# 16_ch_sample-and-hold_card_v4.net
KiCad netlist of a schematic drawn in EAGLE
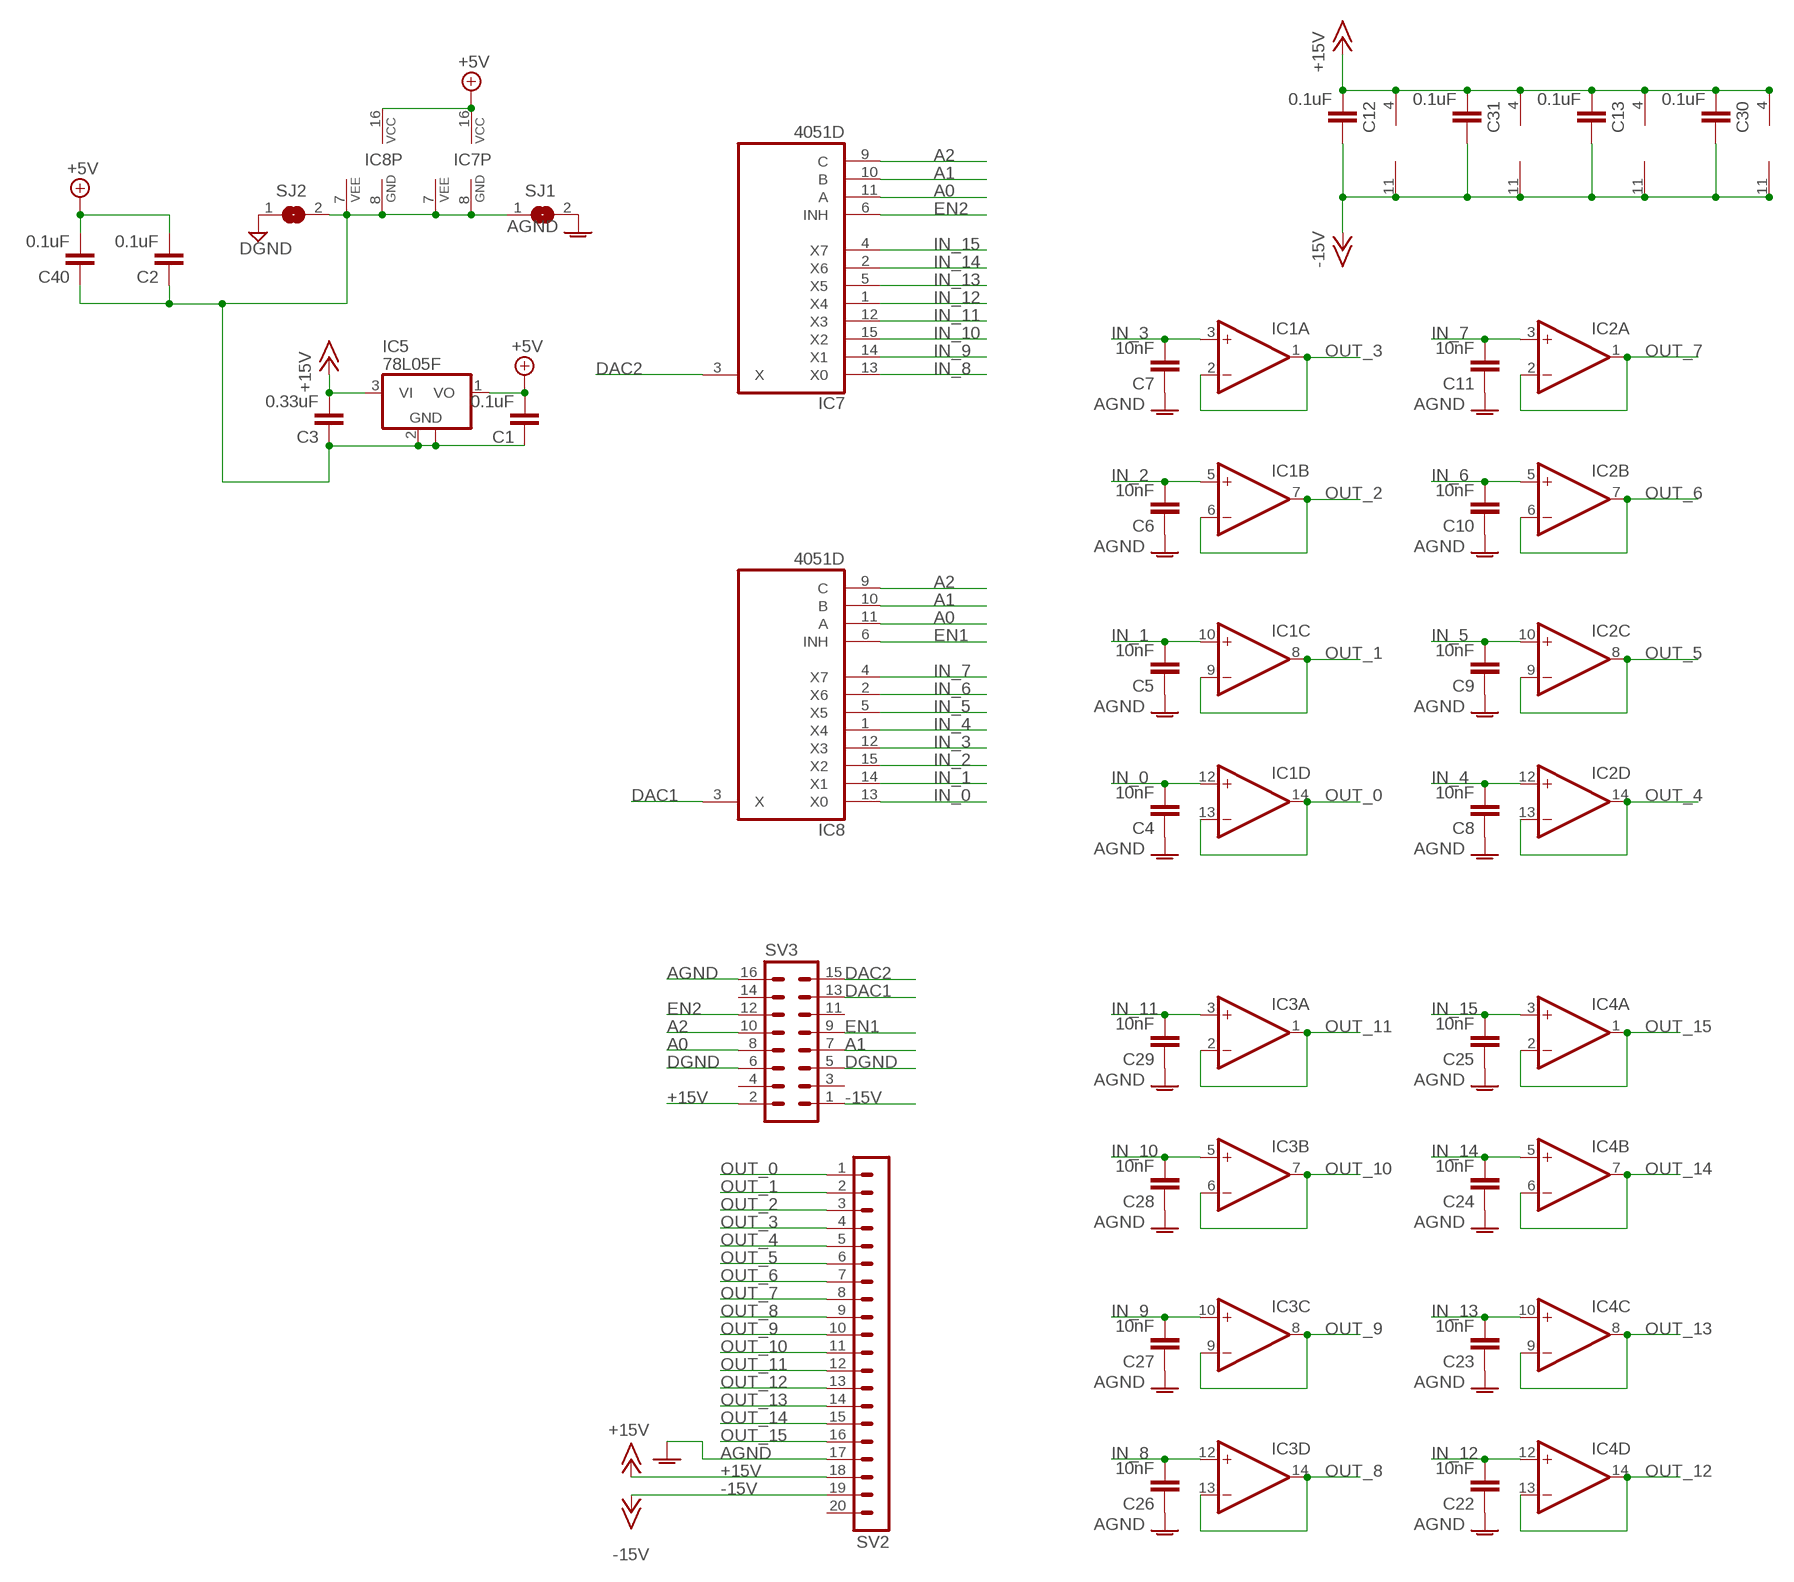
[diagram p0: schematic, sheet 1]

(export (version "E")
  (design (tool "Eeschema 10.0.6"))
  (components
    (comp (ref "C1")
      (value "0.1uF")
      (footprint "eagle-import:C0603")
      (libsource (lib "eagle-import") (part "C-EUC0603"))
    )
    (comp (ref "C2")
      (value "0.1uF")
      (footprint "eagle-import:C0603")
      (libsource (lib "eagle-import") (part "C-EUC0603"))
    )
    (comp (ref "C3")
      (value "0.33uF")
      (footprint "eagle-import:C0603")
      (libsource (lib "eagle-import") (part "C-EUC0603"))
    )
    (comp (ref "C4")
      (value "10nF")
      (footprint "eagle-import:C1206")
      (libsource (lib "eagle-import") (part "C-EUC1206"))
    )
    (comp (ref "C5")
      (value "10nF")
      (footprint "eagle-import:C1206")
      (libsource (lib "eagle-import") (part "C-EUC1206"))
    )
    (comp (ref "C6")
      (value "10nF")
      (footprint "eagle-import:C1206")
      (libsource (lib "eagle-import") (part "C-EUC1206"))
    )
    (comp (ref "C7")
      (value "10nF")
      (footprint "eagle-import:C1206")
      (libsource (lib "eagle-import") (part "C-EUC1206"))
    )
    (comp (ref "C8")
      (value "10nF")
      (footprint "eagle-import:C1206")
      (libsource (lib "eagle-import") (part "C-EUC1206"))
    )
    (comp (ref "C9")
      (value "10nF")
      (footprint "eagle-import:C1206")
      (libsource (lib "eagle-import") (part "C-EUC1206"))
    )
    (comp (ref "C10")
      (value "10nF")
      (footprint "eagle-import:C1206")
      (libsource (lib "eagle-import") (part "C-EUC1206"))
    )
    (comp (ref "C11")
      (value "10nF")
      (footprint "eagle-import:C1206")
      (libsource (lib "eagle-import") (part "C-EUC1206"))
    )
    (comp (ref "C12")
      (value "0.1uF")
      (footprint "eagle-import:C0603")
      (libsource (lib "eagle-import") (part "C-EUC0603"))
    )
    (comp (ref "C13")
      (value "0.1uF")
      (footprint "eagle-import:C0603")
      (libsource (lib "eagle-import") (part "C-EUC0603"))
    )
    (comp (ref "C22")
      (value "10nF")
      (footprint "eagle-import:C1206")
      (libsource (lib "eagle-import") (part "C-EUC1206"))
    )
    (comp (ref "C23")
      (value "10nF")
      (footprint "eagle-import:C1206")
      (libsource (lib "eagle-import") (part "C-EUC1206"))
    )
    (comp (ref "C24")
      (value "10nF")
      (footprint "eagle-import:C1206")
      (libsource (lib "eagle-import") (part "C-EUC1206"))
    )
    (comp (ref "C25")
      (value "10nF")
      (footprint "eagle-import:C1206")
      (libsource (lib "eagle-import") (part "C-EUC1206"))
    )
    (comp (ref "C26")
      (value "10nF")
      (footprint "eagle-import:C1206")
      (libsource (lib "eagle-import") (part "C-EUC1206"))
    )
    (comp (ref "C27")
      (value "10nF")
      (footprint "eagle-import:C1206")
      (libsource (lib "eagle-import") (part "C-EUC1206"))
    )
    (comp (ref "C28")
      (value "10nF")
      (footprint "eagle-import:C1206")
      (libsource (lib "eagle-import") (part "C-EUC1206"))
    )
    (comp (ref "C29")
      (value "10nF")
      (footprint "eagle-import:C1206")
      (libsource (lib "eagle-import") (part "C-EUC1206"))
    )
    (comp (ref "C30")
      (value "0.1uF")
      (footprint "eagle-import:C0603")
      (libsource (lib "eagle-import") (part "C-EUC0603"))
    )
    (comp (ref "C31")
      (value "0.1uF")
      (footprint "eagle-import:C0603")
      (libsource (lib "eagle-import") (part "C-EUC0603"))
    )
    (comp (ref "C40")
      (value "0.1uF")
      (footprint "eagle-import:C0603")
      (libsource (lib "eagle-import") (part "C-EUC0603"))
    )
    (comp (ref "IC1")
      (value "TL074D")
      (footprint "eagle-import:SO14")
      (libsource (lib "eagle-import") (part "TL074D"))
    )
    (comp (ref "IC2")
      (value "TL074D")
      (footprint "eagle-import:SO14")
      (libsource (lib "eagle-import") (part "TL074D"))
    )
    (comp (ref "IC3")
      (value "TL074D")
      (footprint "eagle-import:SO14")
      (libsource (lib "eagle-import") (part "TL074D"))
    )
    (comp (ref "IC4")
      (value "TL074D")
      (footprint "eagle-import:SO14")
      (libsource (lib "eagle-import") (part "TL074D"))
    )
    (comp (ref "IC5")
      (value "78L05F")
      (footprint "eagle-import:SOT89")
      (libsource (lib "eagle-import") (part "78LF05"))
    )
    (comp (ref "IC7")
      (value "4051D")
      (footprint "eagle-import:SO16")
      (libsource (lib "eagle-import") (part "4051D"))
    )
    (comp (ref "IC8")
      (value "4051D")
      (footprint "eagle-import:SO16")
      (libsource (lib "eagle-import") (part "4051D"))
    )
    (comp (ref "SJ1") (value "SJ") (footprint "eagle-import:SJ") (libsource (lib "eagle-import") (part "SJ")))
    (comp (ref "SJ2") (value "SJ") (footprint "eagle-import:SJ") (libsource (lib "eagle-import") (part "SJ")))
    (comp (ref "SV2")
      (value "MA20-1")
      (footprint "eagle-import:MA20-1")
      (libsource (lib "eagle-import") (part "MA20-1"))
    )
    (comp (ref "SV3")
      (value "MA08-2J")
      (footprint "eagle-import:MA08-2J")
      (libsource (lib "eagle-import") (part "MA08-2J"))
    )
  )
  (nets
    (net (code "1") (name "+5V") (class "Default")
      (node (ref "C1") (pin "2") (pinfunction "2_2") (pintype "passive"))
      (node (ref "C2") (pin "2") (pinfunction "2_2") (pintype "passive"))
      (node (ref "C40") (pin "2") (pinfunction "2_2") (pintype "passive"))
      (node (ref "IC5") (pin "1") (pinfunction "VO_1") (pintype "passive"))
      (node (ref "IC7") (pin "16") (pinfunction "VCC_16") (pintype "power_in"))
      (node (ref "IC8") (pin "16") (pinfunction "VCC_16") (pintype "power_in"))
    )
    (net (code "2") (name "+15V") (class "Default")
      (node (ref "C12") (pin "1") (pinfunction "1_1") (pintype "passive"))
      (node (ref "C13") (pin "1") (pinfunction "1_1") (pintype "passive"))
      (node (ref "C3") (pin "2") (pinfunction "2_2") (pintype "passive"))
      (node (ref "C30") (pin "1") (pinfunction "1_1") (pintype "passive"))
      (node (ref "C31") (pin "1") (pinfunction "1_1") (pintype "passive"))
      (node (ref "IC1") (pin "4") (pinfunction "V+_4") (pintype "power_in"))
      (node (ref "IC2") (pin "4") (pinfunction "V+_4") (pintype "power_in"))
      (node (ref "IC3") (pin "4") (pinfunction "V+_4") (pintype "power_in"))
      (node (ref "IC4") (pin "4") (pinfunction "V+_4") (pintype "power_in"))
      (node (ref "IC5") (pin "3") (pinfunction "VI_3") (pintype "input"))
      (node (ref "SV2") (pin "18") (pinfunction "18_18") (pintype "passive"))
      (node (ref "SV3") (pin "2") (pinfunction "2_2") (pintype "passive"))
    )
    (net (code "3") (name "-15V") (class "Default")
      (node (ref "C12") (pin "2") (pinfunction "2_2") (pintype "passive"))
      (node (ref "C13") (pin "2") (pinfunction "2_2") (pintype "passive"))
      (node (ref "C30") (pin "2") (pinfunction "2_2") (pintype "passive"))
      (node (ref "C31") (pin "2") (pinfunction "2_2") (pintype "passive"))
      (node (ref "IC1") (pin "11") (pinfunction "V-_11") (pintype "power_in"))
      (node (ref "IC2") (pin "11") (pinfunction "V-_11") (pintype "power_in"))
      (node (ref "IC3") (pin "11") (pinfunction "V-_11") (pintype "power_in"))
      (node (ref "IC4") (pin "11") (pinfunction "V-_11") (pintype "power_in"))
      (node (ref "SV2") (pin "19") (pinfunction "19_19") (pintype "passive"))
      (node (ref "SV3") (pin "1") (pinfunction "1_1") (pintype "passive"))
    )
    (net (code "4") (name "/A0") (class "Default")
      (node (ref "IC7") (pin "11") (pinfunction "A_11") (pintype "input"))
      (node (ref "IC8") (pin "11") (pinfunction "A_11") (pintype "input"))
      (node (ref "SV3") (pin "8") (pinfunction "8_8") (pintype "passive"))
    )
    (net (code "5") (name "/A1") (class "Default")
      (node (ref "IC7") (pin "10") (pinfunction "B_10") (pintype "input"))
      (node (ref "IC8") (pin "10") (pinfunction "B_10") (pintype "input"))
      (node (ref "SV3") (pin "7") (pinfunction "7_7") (pintype "passive"))
    )
    (net (code "6") (name "/A2") (class "Default")
      (node (ref "IC7") (pin "9") (pinfunction "C_9") (pintype "input"))
      (node (ref "IC8") (pin "9") (pinfunction "C_9") (pintype "input"))
      (node (ref "SV3") (pin "10") (pinfunction "10_10") (pintype "passive"))
    )
    (net (code "7") (name "/DAC1") (class "Default")
      (node (ref "IC8") (pin "3") (pinfunction "X_3") (pintype "bidirectional"))
      (node (ref "SV3") (pin "13") (pinfunction "13_13") (pintype "passive"))
    )
    (net (code "8") (name "/DAC2") (class "Default")
      (node (ref "IC7") (pin "3") (pinfunction "X_3") (pintype "bidirectional"))
      (node (ref "SV3") (pin "15") (pinfunction "15_15") (pintype "passive"))
    )
    (net (code "9") (name "/EN1") (class "Default")
      (node (ref "IC8") (pin "6") (pinfunction "INH_6") (pintype "input"))
      (node (ref "SV3") (pin "9") (pinfunction "9_9") (pintype "passive"))
    )
    (net (code "10") (name "/EN2") (class "Default")
      (node (ref "IC7") (pin "6") (pinfunction "INH_6") (pintype "input"))
      (node (ref "SV3") (pin "12") (pinfunction "12_12") (pintype "passive"))
    )
    (net (code "11") (name "/IN_0") (class "Default")
      (node (ref "C4") (pin "2") (pinfunction "2_2") (pintype "passive"))
      (node (ref "IC1") (pin "12") (pinfunction "+IN_12") (pintype "input"))
      (node (ref "IC8") (pin "13") (pinfunction "X0_13") (pintype "bidirectional"))
    )
    (net (code "12") (name "/IN_1") (class "Default")
      (node (ref "C5") (pin "2") (pinfunction "2_2") (pintype "passive"))
      (node (ref "IC1") (pin "10") (pinfunction "+IN_10") (pintype "input"))
      (node (ref "IC8") (pin "14") (pinfunction "X1_14") (pintype "bidirectional"))
    )
    (net (code "13") (name "/IN_2") (class "Default")
      (node (ref "C6") (pin "2") (pinfunction "2_2") (pintype "passive"))
      (node (ref "IC1") (pin "5") (pinfunction "+IN_5") (pintype "input"))
      (node (ref "IC8") (pin "15") (pinfunction "X2_15") (pintype "bidirectional"))
    )
    (net (code "14") (name "/IN_3") (class "Default")
      (node (ref "C7") (pin "2") (pinfunction "2_2") (pintype "passive"))
      (node (ref "IC1") (pin "3") (pinfunction "+IN_3") (pintype "input"))
      (node (ref "IC8") (pin "12") (pinfunction "X3_12") (pintype "bidirectional"))
    )
    (net (code "15") (name "/IN_4") (class "Default")
      (node (ref "C8") (pin "2") (pinfunction "2_2") (pintype "passive"))
      (node (ref "IC2") (pin "12") (pinfunction "+IN_12") (pintype "input"))
      (node (ref "IC8") (pin "1") (pinfunction "X4_1") (pintype "bidirectional"))
    )
    (net (code "16") (name "/IN_5") (class "Default")
      (node (ref "C9") (pin "2") (pinfunction "2_2") (pintype "passive"))
      (node (ref "IC2") (pin "10") (pinfunction "+IN_10") (pintype "input"))
      (node (ref "IC8") (pin "5") (pinfunction "X5_5") (pintype "bidirectional"))
    )
    (net (code "17") (name "/IN_6") (class "Default")
      (node (ref "C10") (pin "2") (pinfunction "2_2") (pintype "passive"))
      (node (ref "IC2") (pin "5") (pinfunction "+IN_5") (pintype "input"))
      (node (ref "IC8") (pin "2") (pinfunction "X6_2") (pintype "bidirectional"))
    )
    (net (code "18") (name "/IN_7") (class "Default")
      (node (ref "C11") (pin "2") (pinfunction "2_2") (pintype "passive"))
      (node (ref "IC2") (pin "3") (pinfunction "+IN_3") (pintype "input"))
      (node (ref "IC8") (pin "4") (pinfunction "X7_4") (pintype "bidirectional"))
    )
    (net (code "19") (name "/IN_8") (class "Default")
      (node (ref "C26") (pin "2") (pinfunction "2_2") (pintype "passive"))
      (node (ref "IC3") (pin "12") (pinfunction "+IN_12") (pintype "input"))
      (node (ref "IC7") (pin "13") (pinfunction "X0_13") (pintype "bidirectional"))
    )
    (net (code "20") (name "/IN_9") (class "Default")
      (node (ref "C27") (pin "2") (pinfunction "2_2") (pintype "passive"))
      (node (ref "IC3") (pin "10") (pinfunction "+IN_10") (pintype "input"))
      (node (ref "IC7") (pin "14") (pinfunction "X1_14") (pintype "bidirectional"))
    )
    (net (code "21") (name "/IN_10") (class "Default")
      (node (ref "C28") (pin "2") (pinfunction "2_2") (pintype "passive"))
      (node (ref "IC3") (pin "5") (pinfunction "+IN_5") (pintype "input"))
      (node (ref "IC7") (pin "15") (pinfunction "X2_15") (pintype "bidirectional"))
    )
    (net (code "22") (name "/IN_11") (class "Default")
      (node (ref "C29") (pin "2") (pinfunction "2_2") (pintype "passive"))
      (node (ref "IC3") (pin "3") (pinfunction "+IN_3") (pintype "input"))
      (node (ref "IC7") (pin "12") (pinfunction "X3_12") (pintype "bidirectional"))
    )
    (net (code "23") (name "/IN_12") (class "Default")
      (node (ref "C22") (pin "2") (pinfunction "2_2") (pintype "passive"))
      (node (ref "IC4") (pin "12") (pinfunction "+IN_12") (pintype "input"))
      (node (ref "IC7") (pin "1") (pinfunction "X4_1") (pintype "bidirectional"))
    )
    (net (code "24") (name "/IN_13") (class "Default")
      (node (ref "C23") (pin "2") (pinfunction "2_2") (pintype "passive"))
      (node (ref "IC4") (pin "10") (pinfunction "+IN_10") (pintype "input"))
      (node (ref "IC7") (pin "5") (pinfunction "X5_5") (pintype "bidirectional"))
    )
    (net (code "25") (name "/IN_14") (class "Default")
      (node (ref "C24") (pin "2") (pinfunction "2_2") (pintype "passive"))
      (node (ref "IC4") (pin "5") (pinfunction "+IN_5") (pintype "input"))
      (node (ref "IC7") (pin "2") (pinfunction "X6_2") (pintype "bidirectional"))
    )
    (net (code "26") (name "/IN_15") (class "Default")
      (node (ref "C25") (pin "2") (pinfunction "2_2") (pintype "passive"))
      (node (ref "IC4") (pin "3") (pinfunction "+IN_3") (pintype "input"))
      (node (ref "IC7") (pin "4") (pinfunction "X7_4") (pintype "bidirectional"))
    )
    (net (code "27") (name "/OUT_0") (class "Default")
      (node (ref "IC1") (pin "13") (pinfunction "-IN_13") (pintype "input"))
      (node (ref "IC1") (pin "14") (pinfunction "OUT_14") (pintype "output"))
      (node (ref "SV2") (pin "1") (pinfunction "1_1") (pintype "passive"))
    )
    (net (code "28") (name "/OUT_1") (class "Default")
      (node (ref "IC1") (pin "8") (pinfunction "OUT_8") (pintype "output"))
      (node (ref "IC1") (pin "9") (pinfunction "-IN_9") (pintype "input"))
      (node (ref "SV2") (pin "2") (pinfunction "2_2") (pintype "passive"))
    )
    (net (code "29") (name "/OUT_2") (class "Default")
      (node (ref "IC1") (pin "6") (pinfunction "-IN_6") (pintype "input"))
      (node (ref "IC1") (pin "7") (pinfunction "OUT_7") (pintype "output"))
      (node (ref "SV2") (pin "3") (pinfunction "3_3") (pintype "passive"))
    )
    (net (code "30") (name "/OUT_3") (class "Default")
      (node (ref "IC1") (pin "1") (pinfunction "OUT_1") (pintype "output"))
      (node (ref "IC1") (pin "2") (pinfunction "-IN_2") (pintype "input"))
      (node (ref "SV2") (pin "4") (pinfunction "4_4") (pintype "passive"))
    )
    (net (code "31") (name "/OUT_4") (class "Default")
      (node (ref "IC2") (pin "13") (pinfunction "-IN_13") (pintype "input"))
      (node (ref "IC2") (pin "14") (pinfunction "OUT_14") (pintype "output"))
      (node (ref "SV2") (pin "5") (pinfunction "5_5") (pintype "passive"))
    )
    (net (code "32") (name "/OUT_5") (class "Default")
      (node (ref "IC2") (pin "8") (pinfunction "OUT_8") (pintype "output"))
      (node (ref "IC2") (pin "9") (pinfunction "-IN_9") (pintype "input"))
      (node (ref "SV2") (pin "6") (pinfunction "6_6") (pintype "passive"))
    )
    (net (code "33") (name "/OUT_6") (class "Default")
      (node (ref "IC2") (pin "6") (pinfunction "-IN_6") (pintype "input"))
      (node (ref "IC2") (pin "7") (pinfunction "OUT_7") (pintype "output"))
      (node (ref "SV2") (pin "7") (pinfunction "7_7") (pintype "passive"))
    )
    (net (code "34") (name "/OUT_7") (class "Default")
      (node (ref "IC2") (pin "1") (pinfunction "OUT_1") (pintype "output"))
      (node (ref "IC2") (pin "2") (pinfunction "-IN_2") (pintype "input"))
      (node (ref "SV2") (pin "8") (pinfunction "8_8") (pintype "passive"))
    )
    (net (code "35") (name "/OUT_8") (class "Default")
      (node (ref "IC3") (pin "13") (pinfunction "-IN_13") (pintype "input"))
      (node (ref "IC3") (pin "14") (pinfunction "OUT_14") (pintype "output"))
      (node (ref "SV2") (pin "9") (pinfunction "9_9") (pintype "passive"))
    )
    (net (code "36") (name "/OUT_9") (class "Default")
      (node (ref "IC3") (pin "8") (pinfunction "OUT_8") (pintype "output"))
      (node (ref "IC3") (pin "9") (pinfunction "-IN_9") (pintype "input"))
      (node (ref "SV2") (pin "10") (pinfunction "10_10") (pintype "passive"))
    )
    (net (code "37") (name "/OUT_10") (class "Default")
      (node (ref "IC3") (pin "6") (pinfunction "-IN_6") (pintype "input"))
      (node (ref "IC3") (pin "7") (pinfunction "OUT_7") (pintype "output"))
      (node (ref "SV2") (pin "11") (pinfunction "11_11") (pintype "passive"))
    )
    (net (code "38") (name "/OUT_11") (class "Default")
      (node (ref "IC3") (pin "1") (pinfunction "OUT_1") (pintype "output"))
      (node (ref "IC3") (pin "2") (pinfunction "-IN_2") (pintype "input"))
      (node (ref "SV2") (pin "12") (pinfunction "12_12") (pintype "passive"))
    )
    (net (code "39") (name "/OUT_12") (class "Default")
      (node (ref "IC4") (pin "13") (pinfunction "-IN_13") (pintype "input"))
      (node (ref "IC4") (pin "14") (pinfunction "OUT_14") (pintype "output"))
      (node (ref "SV2") (pin "13") (pinfunction "13_13") (pintype "passive"))
    )
    (net (code "40") (name "/OUT_13") (class "Default")
      (node (ref "IC4") (pin "8") (pinfunction "OUT_8") (pintype "output"))
      (node (ref "IC4") (pin "9") (pinfunction "-IN_9") (pintype "input"))
      (node (ref "SV2") (pin "14") (pinfunction "14_14") (pintype "passive"))
    )
    (net (code "41") (name "/OUT_14") (class "Default")
      (node (ref "IC4") (pin "6") (pinfunction "-IN_6") (pintype "input"))
      (node (ref "IC4") (pin "7") (pinfunction "OUT_7") (pintype "output"))
      (node (ref "SV2") (pin "15") (pinfunction "15_15") (pintype "passive"))
    )
    (net (code "42") (name "/OUT_15") (class "Default")
      (node (ref "IC4") (pin "1") (pinfunction "OUT_1") (pintype "output"))
      (node (ref "IC4") (pin "2") (pinfunction "-IN_2") (pintype "input"))
      (node (ref "SV2") (pin "16") (pinfunction "16_16") (pintype "passive"))
    )
    (net (code "43") (name "AGND") (class "Default")
      (node (ref "C10") (pin "1") (pinfunction "1_1") (pintype "passive"))
      (node (ref "C11") (pin "1") (pinfunction "1_1") (pintype "passive"))
      (node (ref "C22") (pin "1") (pinfunction "1_1") (pintype "passive"))
      (node (ref "C23") (pin "1") (pinfunction "1_1") (pintype "passive"))
      (node (ref "C24") (pin "1") (pinfunction "1_1") (pintype "passive"))
      (node (ref "C25") (pin "1") (pinfunction "1_1") (pintype "passive"))
      (node (ref "C26") (pin "1") (pinfunction "1_1") (pintype "passive"))
      (node (ref "C27") (pin "1") (pinfunction "1_1") (pintype "passive"))
      (node (ref "C28") (pin "1") (pinfunction "1_1") (pintype "passive"))
      (node (ref "C29") (pin "1") (pinfunction "1_1") (pintype "passive"))
      (node (ref "C4") (pin "1") (pinfunction "1_1") (pintype "passive"))
      (node (ref "C5") (pin "1") (pinfunction "1_1") (pintype "passive"))
      (node (ref "C6") (pin "1") (pinfunction "1_1") (pintype "passive"))
      (node (ref "C7") (pin "1") (pinfunction "1_1") (pintype "passive"))
      (node (ref "C8") (pin "1") (pinfunction "1_1") (pintype "passive"))
      (node (ref "C9") (pin "1") (pinfunction "1_1") (pintype "passive"))
      (node (ref "SJ1") (pin "2") (pinfunction "2_2") (pintype "passive"))
      (node (ref "SV2") (pin "17") (pinfunction "17_17") (pintype "passive"))
      (node (ref "SV3") (pin "16") (pinfunction "16_16") (pintype "passive"))
    )
    (net (code "44") (name "DGND") (class "Default")
      (node (ref "SJ2") (pin "1") (pinfunction "1_1") (pintype "passive"))
      (node (ref "SV3") (pin "5") (pinfunction "5_5") (pintype "passive"))
      (node (ref "SV3") (pin "6") (pinfunction "6_6") (pintype "passive"))
    )
    (net (code "45") (name "Net-(IC7B-GND)") (class "Default")
      (node (ref "C1") (pin "1") (pinfunction "1_1") (pintype "passive"))
      (node (ref "C2") (pin "1") (pinfunction "1_1") (pintype "passive"))
      (node (ref "C3") (pin "1") (pinfunction "1_1") (pintype "passive"))
      (node (ref "C40") (pin "1") (pinfunction "1_1") (pintype "passive"))
      (node (ref "IC5") (pin "2") (pinfunction "GND_2") (pintype "passive"))
      (node (ref "IC5") (pin "2@1") (pinfunction "GND_2@1") (pintype "passive"))
      (node (ref "IC7") (pin "7") (pinfunction "VEE_7") (pintype "power_in"))
      (node (ref "IC7") (pin "8") (pinfunction "GND_8") (pintype "power_in"))
      (node (ref "IC8") (pin "7") (pinfunction "VEE_7") (pintype "power_in"))
      (node (ref "IC8") (pin "8") (pinfunction "GND_8") (pintype "power_in"))
      (node (ref "SJ1") (pin "1") (pinfunction "1_1") (pintype "passive"))
      (node (ref "SJ2") (pin "2") (pinfunction "2_2") (pintype "passive"))
    )
    (net (code "46") (name "unconnected-(SV2-Pad20)") (class "Default")
      (node (ref "SV2") (pin "20") (pinfunction "20_20") (pintype "passive"))
    )
    (net (code "47") (name "unconnected-(SV3-Pad3)") (class "Default")
      (node (ref "SV3") (pin "3") (pinfunction "3_3") (pintype "passive"))
    )
    (net (code "48") (name "unconnected-(SV3-Pad4)") (class "Default")
      (node (ref "SV3") (pin "4") (pinfunction "4_4") (pintype "passive"))
    )
    (net (code "49") (name "unconnected-(SV3-Pad11)") (class "Default")
      (node (ref "SV3") (pin "11") (pinfunction "11_11") (pintype "passive"))
    )
    (net (code "50") (name "unconnected-(SV3-Pad14)") (class "Default")
      (node (ref "SV3") (pin "14") (pinfunction "14_14") (pintype "passive"))
    )
  )
)
